# Sheet1.net
KiCad netlist of a schematic drawn in Altium Designer
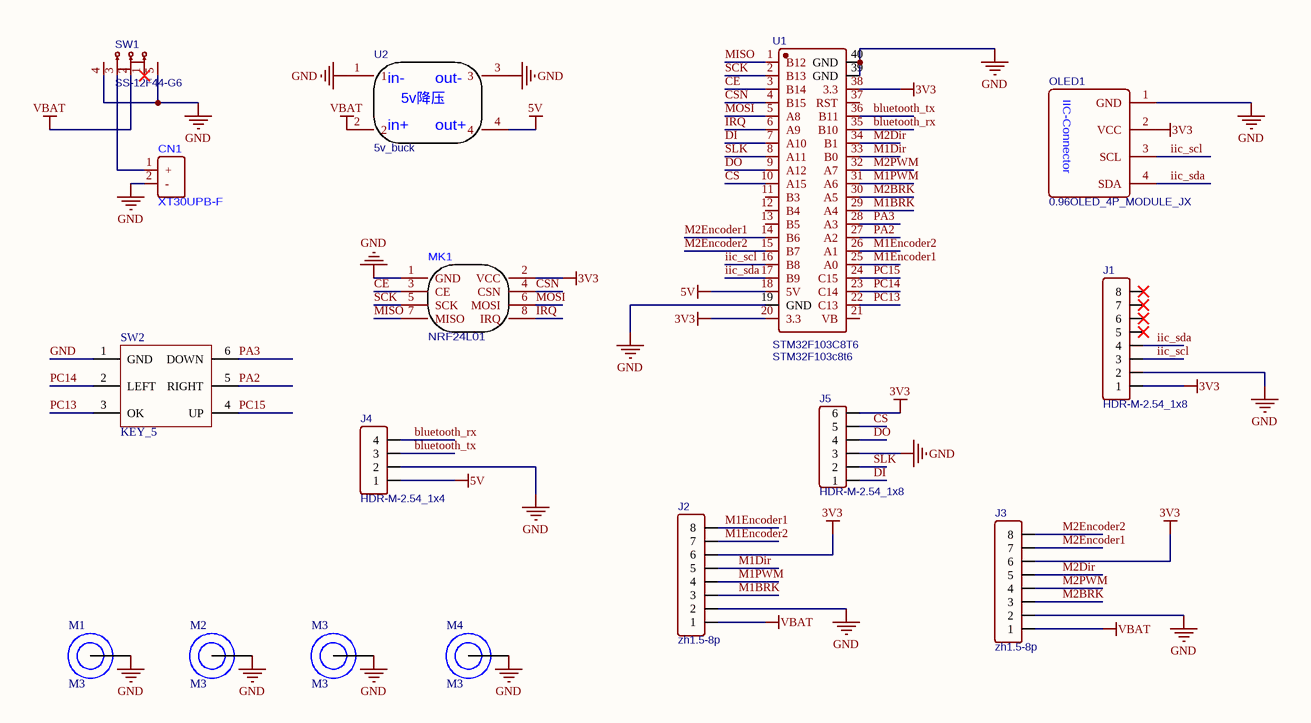
[diagram p0: Sheet1.SchDoc]

(export (version "E")
  (design (tool "Eeschema 10.0.6"))
  (components
    (comp (ref "CN1") (value "XT30UPB-F") (footprint "XT30") (libsource (lib "Schlib1") (part "XT30")))
    (comp (ref "J1")
      (value "HDR-M-2.54_1x8")
      (footprint "HDR-M-2.54_1X8")
      (fields (field (name "BOM_SUPPLIER PART") "C190820") (field (name "CONTRIBUTOR") "LCEDA_Lib"))
      (libsource (lib "Schlib1") (part "HDR-M-2.54_1x8"))
    )
    (comp (ref "J2")
      (value "zh1.5-8p")
      (footprint "ZH1.5-8P")
      (fields (field (name "BOM_SUPPLIER PART") "C190820") (field (name "CONTRIBUTOR") "LCEDA_Lib"))
      (libsource (lib "Schlib1") (part "zh1.5-8p"))
    )
    (comp (ref "J3")
      (value "zh1.5-8p")
      (footprint "ZH1.5-8P")
      (fields (field (name "BOM_SUPPLIER PART") "C190820") (field (name "CONTRIBUTOR") "LCEDA_Lib"))
      (libsource (lib "Schlib1") (part "zh1.5-8p"))
    )
    (comp (ref "J4")
      (value "HDR-M-2.54_1x4")
      (footprint "HDR-M-2.54_1X4")
      (fields (field (name "BOM_SUPPLIER PART") "C124378") (field (name "CONTRIBUTOR") "LCEDA_Lib"))
      (libsource (lib "Schlib1") (part "HDR-M-2.54_1x4"))
    )
    (comp (ref "J5")
      (value "HDR-M-2.54_1x8")
      (footprint "HDR-M-2.54_1X6")
      (fields (field (name "BOM_SUPPLIER PART") "C190820") (field (name "CONTRIBUTOR") "LCEDA_Lib"))
      (libsource (lib "Schlib1") (part "HDR-M-2.54_1x6"))
    )
    (comp (ref "M1") (value "M3") (footprint "M3") (libsource (lib "Schlib1") (part "M3")))
    (comp (ref "M2") (value "M3") (footprint "M3") (libsource (lib "Schlib1") (part "M3")))
    (comp (ref "M3") (value "M3") (footprint "M3") (libsource (lib "Schlib1") (part "M3")))
    (comp (ref "M4") (value "M3") (footprint "M3") (libsource (lib "Schlib1") (part "M3")))
    (comp (ref "MK1") (value "NRF24L01") (footprint "NRF24L01") (libsource (lib "Schlib1") (part "NRF24L01")))
    (comp (ref "OLED1")
      (value "0.96OLED_4P_MODULE_JX")
      (footprint "0.96OLED_4P")
      (fields (field (name "BOM_SUPPLIER PART") "C9900004566") (field (name "CONTRIBUTOR") "LCSC"))
      (libsource (lib "Schlib1") (part "0.96OLED_4P_MODULE_JX"))
    )
    (comp (ref "SW1")
      (value "SS-12F44-G6")
      (footprint "SW-TH_SS-12F44-GX")
      (fields (field (name "BOM_SUPPLIER PART") "C698210") (field (name "CONTRIBUTOR") "LCSC"))
      (libsource (lib "Schlib1") (part "SS-12F44-G6"))
    )
    (comp (ref "SW2")
      (value "KEY_5")
      (footprint "KEY_5")
      (description "五向导航按钮")
      (libsource (lib "Schlib1") (part "KEY_5"))
    )
    (comp (ref "U1")
      (value "STM32F103c8t6")
      (footprint "stm32f103coreboard")
      (fields (field (name "CONTRIBUTOR") "fsxqn"))
      (libsource (lib "Schlib1") (part "STM32F103c8t6"))
    )
    (comp (ref "U2")
      (value "5v_buck")
      (footprint "5V_BUCK")
      (fields (field (name "CONTRIBUTOR") "fsxqn"))
      (libsource (lib "Schlib1") (part "5v_buck"))
    )
  )
  (nets
    (net (code "1") (name "/CE") (class "Default")
      (node (ref "MK1") (pin "3") (pinfunction "CE_3") (pintype "passive"))
      (node (ref "U1") (pin "3") (pinfunction "B14_3") (pintype "passive"))
    )
    (net (code "2") (name "/CS") (class "Default")
      (node (ref "J5") (pin "5") (pinfunction "5_5") (pintype "passive"))
      (node (ref "U1") (pin "10") (pinfunction "A15_10") (pintype "passive"))
    )
    (net (code "3") (name "/CSN") (class "Default")
      (node (ref "MK1") (pin "4") (pinfunction "CSN_4") (pintype "passive"))
      (node (ref "U1") (pin "4") (pinfunction "B15_4") (pintype "passive"))
    )
    (net (code "4") (name "/DI") (class "Default")
      (node (ref "J5") (pin "1") (pinfunction "1_1") (pintype "passive"))
      (node (ref "U1") (pin "7") (pinfunction "A10_7") (pintype "passive"))
    )
    (net (code "5") (name "/DO") (class "Default")
      (node (ref "J5") (pin "4") (pinfunction "4_4") (pintype "passive"))
      (node (ref "U1") (pin "9") (pinfunction "A12_9") (pintype "passive"))
    )
    (net (code "6") (name "/IRQ") (class "Default")
      (node (ref "MK1") (pin "8") (pinfunction "IRQ_8") (pintype "passive"))
      (node (ref "U1") (pin "6") (pinfunction "A9_6") (pintype "passive"))
    )
    (net (code "7") (name "/M1BRK") (class "Default")
      (node (ref "J2") (pin "3") (pinfunction "3_3") (pintype "passive"))
      (node (ref "U1") (pin "29") (pinfunction "A4_29") (pintype "passive"))
    )
    (net (code "8") (name "/M1Dir") (class "Default")
      (node (ref "J2") (pin "5") (pinfunction "5_5") (pintype "passive"))
      (node (ref "U1") (pin "33") (pinfunction "B0_33") (pintype "passive"))
    )
    (net (code "9") (name "/M1Encoder1") (class "Default")
      (node (ref "J2") (pin "8") (pinfunction "8_8") (pintype "passive"))
      (node (ref "U1") (pin "25") (pinfunction "A0_25") (pintype "passive"))
    )
    (net (code "10") (name "/M1Encoder2") (class "Default")
      (node (ref "J2") (pin "7") (pinfunction "7_7") (pintype "passive"))
      (node (ref "U1") (pin "26") (pinfunction "A1_26") (pintype "passive"))
    )
    (net (code "11") (name "/M1PWM") (class "Default")
      (node (ref "J2") (pin "4") (pinfunction "4_4") (pintype "passive"))
      (node (ref "U1") (pin "31") (pinfunction "A6_31") (pintype "passive"))
    )
    (net (code "12") (name "/M2BRK") (class "Default")
      (node (ref "J3") (pin "3") (pinfunction "3_3") (pintype "passive"))
      (node (ref "U1") (pin "30") (pinfunction "A5_30") (pintype "passive"))
    )
    (net (code "13") (name "/M2Dir") (class "Default")
      (node (ref "J3") (pin "5") (pinfunction "5_5") (pintype "passive"))
      (node (ref "U1") (pin "34") (pinfunction "B1_34") (pintype "passive"))
    )
    (net (code "14") (name "/M2Encoder1") (class "Default")
      (node (ref "J3") (pin "7") (pinfunction "7_7") (pintype "passive"))
      (node (ref "U1") (pin "14") (pinfunction "B6_14") (pintype "passive"))
    )
    (net (code "15") (name "/M2Encoder2") (class "Default")
      (node (ref "J3") (pin "8") (pinfunction "8_8") (pintype "passive"))
      (node (ref "U1") (pin "15") (pinfunction "B7_15") (pintype "passive"))
    )
    (net (code "16") (name "/M2PWM") (class "Default")
      (node (ref "J3") (pin "4") (pinfunction "4_4") (pintype "passive"))
      (node (ref "U1") (pin "32") (pinfunction "A7_32") (pintype "passive"))
    )
    (net (code "17") (name "/MISO") (class "Default")
      (node (ref "MK1") (pin "7") (pinfunction "MISO_7") (pintype "passive"))
      (node (ref "U1") (pin "1") (pinfunction "B12_1") (pintype "passive"))
    )
    (net (code "18") (name "/MOSI") (class "Default")
      (node (ref "MK1") (pin "6") (pinfunction "MOSI_6") (pintype "passive"))
      (node (ref "U1") (pin "5") (pinfunction "A8_5") (pintype "passive"))
    )
    (net (code "19") (name "/PA2") (class "Default")
      (node (ref "SW2") (pin "5") (pinfunction "RIGHT_5") (pintype "passive"))
      (node (ref "U1") (pin "27") (pinfunction "A2_27") (pintype "passive"))
    )
    (net (code "20") (name "/PA3") (class "Default")
      (node (ref "SW2") (pin "6") (pinfunction "DOWN_6") (pintype "passive"))
      (node (ref "U1") (pin "28") (pinfunction "A3_28") (pintype "passive"))
    )
    (net (code "21") (name "/PC13") (class "Default")
      (node (ref "SW2") (pin "3") (pinfunction "OK_3") (pintype "passive"))
      (node (ref "U1") (pin "22") (pinfunction "C13_22") (pintype "passive"))
    )
    (net (code "22") (name "/PC14") (class "Default")
      (node (ref "SW2") (pin "2") (pinfunction "LEFT_2") (pintype "passive"))
      (node (ref "U1") (pin "23") (pinfunction "C14_23") (pintype "passive"))
    )
    (net (code "23") (name "/PC15") (class "Default")
      (node (ref "SW2") (pin "4") (pinfunction "UP_4") (pintype "passive"))
      (node (ref "U1") (pin "24") (pinfunction "C15_24") (pintype "passive"))
    )
    (net (code "24") (name "/SCK") (class "Default")
      (node (ref "MK1") (pin "5") (pinfunction "SCK_5") (pintype "passive"))
      (node (ref "U1") (pin "2") (pinfunction "B13_2") (pintype "passive"))
    )
    (net (code "25") (name "/SLK") (class "Default")
      (node (ref "J5") (pin "2") (pinfunction "2_2") (pintype "passive"))
      (node (ref "U1") (pin "8") (pinfunction "A11_8") (pintype "passive"))
    )
    (net (code "26") (name "/bluetooth_rx") (class "Default")
      (node (ref "J4") (pin "4") (pinfunction "4_4") (pintype "passive"))
      (node (ref "U1") (pin "35") (pinfunction "B10_35") (pintype "passive"))
    )
    (net (code "27") (name "/bluetooth_tx") (class "Default")
      (node (ref "J4") (pin "3") (pinfunction "3_3") (pintype "passive"))
      (node (ref "U1") (pin "36") (pinfunction "B11_36") (pintype "passive"))
    )
    (net (code "28") (name "/iic_scl") (class "Default")
      (node (ref "J1") (pin "3") (pinfunction "3_3") (pintype "passive"))
      (node (ref "OLED1") (pin "3") (pinfunction "SCL_3") (pintype "passive"))
      (node (ref "U1") (pin "16") (pinfunction "B8_16") (pintype "passive"))
    )
    (net (code "29") (name "/iic_sda") (class "Default")
      (node (ref "J1") (pin "4") (pinfunction "4_4") (pintype "passive"))
      (node (ref "OLED1") (pin "4") (pinfunction "SDA_4") (pintype "passive"))
      (node (ref "U1") (pin "17") (pinfunction "B9_17") (pintype "passive"))
    )
    (net (code "30") (name "3V3") (class "Default")
      (node (ref "J1") (pin "1") (pinfunction "1_1") (pintype "passive"))
      (node (ref "J2") (pin "6") (pinfunction "6_6") (pintype "passive"))
      (node (ref "J3") (pin "6") (pinfunction "6_6") (pintype "passive"))
      (node (ref "J5") (pin "6") (pinfunction "6_6") (pintype "passive"))
      (node (ref "MK1") (pin "2") (pinfunction "VCC_2") (pintype "passive"))
      (node (ref "OLED1") (pin "2") (pinfunction "VCC_2") (pintype "passive"))
      (node (ref "U1") (pin "20") (pinfunction "3.3_20") (pintype "passive"))
      (node (ref "U1") (pin "38") (pinfunction "3.3_38") (pintype "passive"))
    )
    (net (code "31") (name "5V") (class "Default")
      (node (ref "J4") (pin "1") (pinfunction "1_1") (pintype "passive"))
      (node (ref "U1") (pin "18") (pinfunction "5V_18") (pintype "passive"))
      (node (ref "U2") (pin "4") (pinfunction "4_4") (pintype "passive"))
    )
    (net (code "32") (name "GND") (class "Default")
      (node (ref "CN1") (pin "2") (pinfunction "-_2") (pintype "passive"))
      (node (ref "J1") (pin "2") (pinfunction "2_2") (pintype "passive"))
      (node (ref "J2") (pin "2") (pinfunction "2_2") (pintype "passive"))
      (node (ref "J3") (pin "2") (pinfunction "2_2") (pintype "passive"))
      (node (ref "J4") (pin "2") (pinfunction "2_2") (pintype "passive"))
      (node (ref "J5") (pin "3") (pinfunction "3_3") (pintype "passive"))
      (node (ref "M1") (pin "1") (pinfunction "1_1") (pintype "passive"))
      (node (ref "M2") (pin "1") (pinfunction "1_1") (pintype "passive"))
      (node (ref "M3") (pin "1") (pinfunction "1_1") (pintype "passive"))
      (node (ref "M4") (pin "1") (pinfunction "1_1") (pintype "passive"))
      (node (ref "MK1") (pin "1") (pinfunction "GND_1") (pintype "passive"))
      (node (ref "OLED1") (pin "1") (pinfunction "GND_1") (pintype "passive"))
      (node (ref "SW1") (pin "4") (pinfunction "4_4") (pintype "passive"))
      (node (ref "SW1") (pin "5") (pinfunction "5_5") (pintype "passive"))
      (node (ref "SW2") (pin "1") (pinfunction "GND_1") (pintype "passive"))
      (node (ref "U1") (pin "19") (pinfunction "GND_19") (pintype "passive"))
      (node (ref "U1") (pin "39") (pinfunction "GND_39") (pintype "passive"))
      (node (ref "U1") (pin "40") (pinfunction "GND_40") (pintype "passive"))
      (node (ref "U2") (pin "1") (pinfunction "1_1") (pintype "passive"))
      (node (ref "U2") (pin "3") (pinfunction "3_3") (pintype "passive"))
    )
    (net (code "33") (name "Net-(CN1-+)") (class "Default")
      (node (ref "CN1") (pin "1") (pinfunction "+_1") (pintype "passive"))
      (node (ref "SW1") (pin "3") (pinfunction "3_3") (pintype "passive"))
    )
    (net (code "34") (name "VBAT") (class "Default")
      (node (ref "J2") (pin "1") (pinfunction "1_1") (pintype "passive"))
      (node (ref "J3") (pin "1") (pinfunction "1_1") (pintype "passive"))
      (node (ref "SW1") (pin "2") (pinfunction "2_2") (pintype "passive"))
      (node (ref "U2") (pin "2") (pinfunction "2_2") (pintype "passive"))
    )
    (net (code "35") (name "unconnected-(J1-Pad5)") (class "Default")
      (node (ref "J1") (pin "5") (pinfunction "5_5") (pintype "passive+no_connect"))
    )
    (net (code "36") (name "unconnected-(J1-Pad6)") (class "Default")
      (node (ref "J1") (pin "6") (pinfunction "6_6") (pintype "passive+no_connect"))
    )
    (net (code "37") (name "unconnected-(J1-Pad7)") (class "Default")
      (node (ref "J1") (pin "7") (pinfunction "7_7") (pintype "passive+no_connect"))
    )
    (net (code "38") (name "unconnected-(J1-Pad8)") (class "Default")
      (node (ref "J1") (pin "8") (pinfunction "8_8") (pintype "passive+no_connect"))
    )
    (net (code "39") (name "unconnected-(SW1-Pad1)") (class "Default")
      (node (ref "SW1") (pin "1") (pinfunction "1_1") (pintype "passive+no_connect"))
    )
    (net (code "40") (name "unconnected-(U1-B3-Pad11)") (class "Default")
      (node (ref "U1") (pin "11") (pinfunction "B3_11") (pintype "passive"))
    )
    (net (code "41") (name "unconnected-(U1-B4-Pad12)") (class "Default")
      (node (ref "U1") (pin "12") (pinfunction "B4_12") (pintype "passive"))
    )
    (net (code "42") (name "unconnected-(U1-B5-Pad13)") (class "Default")
      (node (ref "U1") (pin "13") (pinfunction "B5_13") (pintype "passive"))
    )
    (net (code "43") (name "unconnected-(U1-RST-Pad37)") (class "Default")
      (node (ref "U1") (pin "37") (pinfunction "RST_37") (pintype "passive"))
    )
    (net (code "44") (name "unconnected-(U1-VB-Pad21)") (class "Default")
      (node (ref "U1") (pin "21") (pinfunction "VB_21") (pintype "passive"))
    )
  )
)
